# Sheet_2_nizovie.net
KiCad netlist of a schematic drawn in Altium Designer
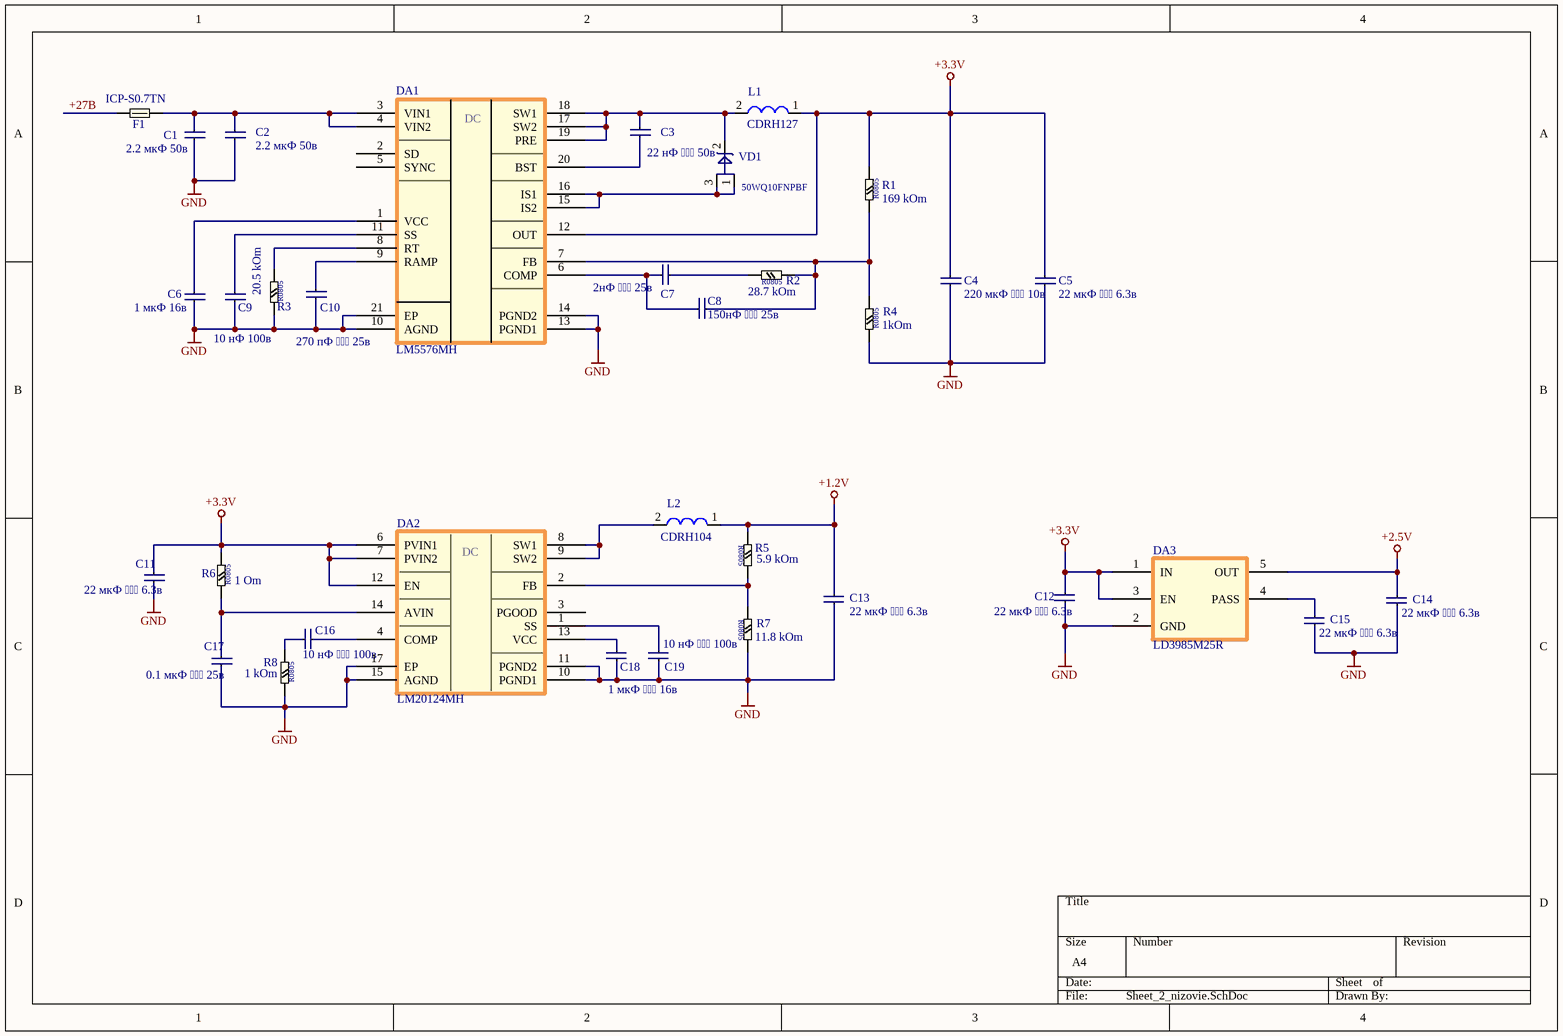
[diagram p0: Sheet_2_nizovie.SchDoc]

(export (version "E")
  (design (tool "Eeschema 10.0.6"))
  (components
    (comp (ref "C1")
      (value "2.2 мкФ 50в")
      (footprint "FP_0805")
      (libsource (lib "Schlib_nizovie") (part "C0805"))
    )
    (comp (ref "C2")
      (value "2.2 мкФ 50в")
      (footprint "FP_0805")
      (libsource (lib "Schlib_nizovie") (part "C0805"))
    )
    (comp (ref "C3")
      (value "22 нФ  50в")
      (footprint "FP_0805")
      (libsource (lib "Schlib_nizovie") (part "C0805"))
    )
    (comp (ref "C4")
      (value "220 мкФ  10в")
      (footprint "TYPE_D")
      (libsource (lib "Schlib_nizovie") (part "C0805"))
    )
    (comp (ref "C5")
      (value "22 мкФ  6.3в")
      (footprint "FP_0805")
      (libsource (lib "Schlib_nizovie") (part "C0805"))
    )
    (comp (ref "C6")
      (value "1 мкФ 16в")
      (footprint "FP_0805")
      (libsource (lib "Schlib_nizovie") (part "C0805"))
    )
    (comp (ref "C7")
      (value "2нФ  25в")
      (footprint "FP_0805")
      (libsource (lib "Schlib_nizovie") (part "C0805"))
    )
    (comp (ref "C8")
      (value "150нФ  25в")
      (footprint "FP_0805")
      (libsource (lib "Schlib_nizovie") (part "C0805"))
    )
    (comp (ref "C9")
      (value "10 нФ 100в")
      (footprint "FP_0805")
      (libsource (lib "Schlib_nizovie") (part "C0805"))
    )
    (comp (ref "C10")
      (value "270 пФ  25в")
      (footprint "FP_0805")
      (libsource (lib "Schlib_nizovie") (part "C0805"))
    )
    (comp (ref "C11")
      (value "22 мкФ  6.3в")
      (footprint "FP_0805")
      (libsource (lib "Schlib_nizovie") (part "C0805"))
    )
    (comp (ref "C12")
      (value "22 мкФ  6.3в")
      (footprint "FP_0805")
      (libsource (lib "Schlib_nizovie") (part "C0805"))
    )
    (comp (ref "C13")
      (value "22 мкФ  6.3в")
      (footprint "FP_0805")
      (libsource (lib "Schlib_nizovie") (part "C0805"))
    )
    (comp (ref "C14")
      (value "22 мкФ  6.3в")
      (footprint "FP_0805")
      (libsource (lib "Schlib_nizovie") (part "C0805"))
    )
    (comp (ref "C15")
      (value "22 мкФ  6.3в")
      (footprint "FP_0805")
      (libsource (lib "Schlib_nizovie") (part "C0805"))
    )
    (comp (ref "C16")
      (value "10 нФ  100в")
      (footprint "FP_0805")
      (libsource (lib "Schlib_nizovie") (part "C0805"))
    )
    (comp (ref "C17")
      (value "0.1 мкФ  25в")
      (footprint "FP_0805")
      (libsource (lib "Schlib_nizovie") (part "C0805"))
    )
    (comp (ref "C18")
      (value "1 мкФ  16в")
      (footprint "FP_0805")
      (libsource (lib "Schlib_nizovie") (part "C0805"))
    )
    (comp (ref "C19")
      (value "10 нФ  100в")
      (footprint "FP_0805")
      (libsource (lib "Schlib_nizovie") (part "C0805"))
    )
    (comp (ref "DA1")
      (value "LM5576MH")
      (footprint "LM5576")
      (libsource (lib "Schlib_nizovie") (part "LM5576MH"))
    )
    (comp (ref "DA2")
      (value "LM20124MH")
      (footprint "LM20124")
      (libsource (lib "Schlib_nizovie") (part "LM20124MH"))
    )
    (comp (ref "DA3")
      (value "LD3985M25R")
      (footprint "LD3985")
      (libsource (lib "Schlib_nizovie") (part "LD3985M25R"))
    )
    (comp (ref "F1")
      (value "ICP-S0.7TN")
      (footprint "ICP-S0.7")
      (libsource (lib "Schlib_nizovie") (part "ICP-S0.7TN"))
    )
    (comp (ref "L1")
      (value "CDRH127")
      (footprint "CDRH127")
      (libsource (lib "Schlib_nizovie") (part "CDRH127"))
    )
    (comp (ref "L2")
      (value "CDRH104")
      (footprint "CDRH104R")
      (libsource (lib "Schlib_nizovie") (part "CDRH104"))
    )
    (comp (ref "R1")
      (value "169 kOm")
      (footprint "FP_0805")
      (description "1kOm")
      (libsource (lib "Schlib_nizovie") (part "R0805"))
    )
    (comp (ref "R2")
      (value "28.7 kOm")
      (footprint "FP_0805")
      (description "1kOm")
      (libsource (lib "") (part "R0805_2"))
    )
    (comp (ref "R3")
      (value "20.5 kOm")
      (footprint "FP_0805")
      (description "1kOm")
      (libsource (lib "Schlib_nizovie") (part "R0805"))
    )
    (comp (ref "R4") (value "1kOm") (footprint "FP_0805") (libsource (lib "Schlib_nizovie") (part "R0805")))
    (comp (ref "R5")
      (value "5.9 kOm")
      (footprint "FP_0805")
      (description "1kOm")
      (libsource (lib "") (part "R0805_1"))
    )
    (comp (ref "R6")
      (value "1 Om")
      (footprint "FP_0805")
      (description "1kOm")
      (libsource (lib "Schlib_nizovie") (part "R0805"))
    )
    (comp (ref "R7")
      (value "11.8 kOm")
      (footprint "FP_0805")
      (description "1kOm")
      (libsource (lib "") (part "R0805_1"))
    )
    (comp (ref "R8")
      (value "1 kOm")
      (footprint "FP_0805")
      (description "1kOm")
      (libsource (lib "Schlib_nizovie") (part "R0805"))
    )
    (comp (ref "VD1")
      (value "50WQ10FNPBF")
      (footprint "50WQ06")
      (libsource (lib "Schlib_nizovie") (part "50WQ10FNPBF"))
    )
  )
  (nets
    (net (code "1") (name "+1.2V") (class "Default")
      (node (ref "C13") (pin "1") (pinfunction "1_1") (pintype "passive"))
      (node (ref "L2") (pin "1") (pinfunction "1_1") (pintype "passive"))
      (node (ref "R5") (pin "1") (pinfunction "1_1") (pintype "passive"))
    )
    (net (code "2") (name "+2.5V") (class "Default")
      (node (ref "C14") (pin "1") (pinfunction "1_1") (pintype "passive"))
      (node (ref "DA3") (pin "5") (pinfunction "OUT_5") (pintype "passive"))
    )
    (net (code "3") (name "+3.3V") (class "Default")
      (node (ref "C11") (pin "2") (pinfunction "2_2") (pintype "passive"))
      (node (ref "C12") (pin "1") (pinfunction "1_1") (pintype "passive"))
      (node (ref "C4") (pin "2") (pinfunction "2_2") (pintype "passive"))
      (node (ref "C5") (pin "2") (pinfunction "2_2") (pintype "passive"))
      (node (ref "DA1") (pin "12") (pinfunction "OUT_12") (pintype "passive"))
      (node (ref "DA2") (pin "12") (pinfunction "EN_12") (pintype "passive"))
      (node (ref "DA2") (pin "6") (pinfunction "PVIN1_6") (pintype "passive"))
      (node (ref "DA2") (pin "7") (pinfunction "PVIN2_7") (pintype "passive"))
      (node (ref "DA3") (pin "1") (pinfunction "IN_1") (pintype "passive"))
      (node (ref "DA3") (pin "3") (pinfunction "EN_3") (pintype "passive"))
      (node (ref "L1") (pin "1") (pinfunction "1_1") (pintype "passive"))
      (node (ref "R1") (pin "2") (pinfunction "2_2") (pintype "passive"))
      (node (ref "R6") (pin "2") (pinfunction "2_2") (pintype "passive"))
    )
    (net (code "4") (name "/+27В") (class "Default")
      (node (ref "F1") (pin "1") (pinfunction "1_1") (pintype "passive"))
    )
    (net (code "5") (name "GND") (class "Default")
      (node (ref "C1") (pin "1") (pinfunction "1_1") (pintype "passive"))
      (node (ref "C10") (pin "1") (pinfunction "1_1") (pintype "passive"))
      (node (ref "C11") (pin "1") (pinfunction "1_1") (pintype "passive"))
      (node (ref "C12") (pin "2") (pinfunction "2_2") (pintype "passive"))
      (node (ref "C13") (pin "2") (pinfunction "2_2") (pintype "passive"))
      (node (ref "C14") (pin "2") (pinfunction "2_2") (pintype "passive"))
      (node (ref "C15") (pin "2") (pinfunction "2_2") (pintype "passive"))
      (node (ref "C17") (pin "1") (pinfunction "1_1") (pintype "passive"))
      (node (ref "C18") (pin "2") (pinfunction "2_2") (pintype "passive"))
      (node (ref "C19") (pin "2") (pinfunction "2_2") (pintype "passive"))
      (node (ref "C2") (pin "1") (pinfunction "1_1") (pintype "passive"))
      (node (ref "C4") (pin "1") (pinfunction "1_1") (pintype "passive"))
      (node (ref "C5") (pin "1") (pinfunction "1_1") (pintype "passive"))
      (node (ref "C6") (pin "1") (pinfunction "1_1") (pintype "passive"))
      (node (ref "C9") (pin "1") (pinfunction "1_1") (pintype "passive"))
      (node (ref "DA1") (pin "10") (pinfunction "AGND_10") (pintype "passive"))
      (node (ref "DA1") (pin "13") (pinfunction "PGND1_13") (pintype "passive"))
      (node (ref "DA1") (pin "14") (pinfunction "PGND2_14") (pintype "passive"))
      (node (ref "DA1") (pin "21") (pinfunction "EP_21") (pintype "passive"))
      (node (ref "DA2") (pin "10") (pinfunction "PGND1_10") (pintype "passive"))
      (node (ref "DA2") (pin "11") (pinfunction "PGND2_11") (pintype "passive"))
      (node (ref "DA2") (pin "15") (pinfunction "AGND_15") (pintype "passive"))
      (node (ref "DA2") (pin "17") (pinfunction "EP_17") (pintype "passive"))
      (node (ref "DA3") (pin "2") (pinfunction "GND_2") (pintype "passive"))
      (node (ref "R3") (pin "1") (pinfunction "1_1") (pintype "passive"))
      (node (ref "R4") (pin "1") (pinfunction "1_1") (pintype "passive"))
      (node (ref "R7") (pin "2") (pinfunction "2_2") (pintype "passive"))
      (node (ref "R8") (pin "1") (pinfunction "1_1") (pintype "passive"))
    )
    (net (code "6") (name "Net-(C7-Pad1)") (class "Default")
      (node (ref "C7") (pin "1") (pinfunction "1_1") (pintype "passive"))
      (node (ref "R2") (pin "1") (pinfunction "1_1") (pintype "passive"))
    )
    (net (code "7") (name "Net-(C16-Pad2)") (class "Default")
      (node (ref "C16") (pin "2") (pinfunction "2_2") (pintype "passive"))
      (node (ref "R8") (pin "2") (pinfunction "2_2") (pintype "passive"))
    )
    (net (code "8") (name "Net-(DA1-BST)") (class "Default")
      (node (ref "C3") (pin "1") (pinfunction "1_1") (pintype "passive"))
      (node (ref "DA1") (pin "20") (pinfunction "BST_20") (pintype "passive"))
    )
    (net (code "9") (name "Net-(DA1-COMP)") (class "Default")
      (node (ref "C7") (pin "2") (pinfunction "2_2") (pintype "passive"))
      (node (ref "C8") (pin "2") (pinfunction "2_2") (pintype "passive"))
      (node (ref "DA1") (pin "6") (pinfunction "COMP_6") (pintype "passive"))
    )
    (net (code "10") (name "Net-(DA1-FB)") (class "Default")
      (node (ref "C8") (pin "1") (pinfunction "1_1") (pintype "passive"))
      (node (ref "DA1") (pin "7") (pinfunction "FB_7") (pintype "passive"))
      (node (ref "R1") (pin "1") (pinfunction "1_1") (pintype "passive"))
      (node (ref "R2") (pin "2") (pinfunction "2_2") (pintype "passive"))
      (node (ref "R4") (pin "2") (pinfunction "2_2") (pintype "passive"))
    )
    (net (code "11") (name "Net-(DA1-IS1)") (class "Default")
      (node (ref "DA1") (pin "15") (pinfunction "IS2_15") (pintype "passive"))
      (node (ref "DA1") (pin "16") (pinfunction "IS1_16") (pintype "passive"))
      (node (ref "VD1") (pin "1") (pinfunction "1_1") (pintype "passive"))
      (node (ref "VD1") (pin "3") (pinfunction "3_3") (pintype "passive"))
    )
    (net (code "12") (name "Net-(DA1-PRE)") (class "Default")
      (node (ref "C3") (pin "2") (pinfunction "2_2") (pintype "passive"))
      (node (ref "DA1") (pin "17") (pinfunction "SW2_17") (pintype "passive"))
      (node (ref "DA1") (pin "18") (pinfunction "SW1_18") (pintype "passive"))
      (node (ref "DA1") (pin "19") (pinfunction "PRE_19") (pintype "passive"))
      (node (ref "L1") (pin "2") (pinfunction "2_2") (pintype "passive"))
      (node (ref "VD1") (pin "2") (pinfunction "2_2") (pintype "passive"))
    )
    (net (code "13") (name "Net-(DA1-RAMP)") (class "Default")
      (node (ref "C10") (pin "2") (pinfunction "2_2") (pintype "passive"))
      (node (ref "DA1") (pin "9") (pinfunction "RAMP_9") (pintype "passive"))
    )
    (net (code "14") (name "Net-(DA1-RT)") (class "Default")
      (node (ref "DA1") (pin "8") (pinfunction "RT_8") (pintype "passive"))
      (node (ref "R3") (pin "2") (pinfunction "2_2") (pintype "passive"))
    )
    (net (code "15") (name "Net-(DA1-SS)") (class "Default")
      (node (ref "C9") (pin "2") (pinfunction "2_2") (pintype "passive"))
      (node (ref "DA1") (pin "11") (pinfunction "SS_11") (pintype "passive"))
    )
    (net (code "16") (name "Net-(DA1-VCC)") (class "Default")
      (node (ref "C6") (pin "2") (pinfunction "2_2") (pintype "passive"))
      (node (ref "DA1") (pin "1") (pinfunction "VCC_1") (pintype "passive"))
    )
    (net (code "17") (name "Net-(DA1-VIN1)") (class "Default")
      (node (ref "C1") (pin "2") (pinfunction "2_2") (pintype "passive"))
      (node (ref "C2") (pin "2") (pinfunction "2_2") (pintype "passive"))
      (node (ref "DA1") (pin "3") (pinfunction "VIN1_3") (pintype "passive"))
      (node (ref "DA1") (pin "4") (pinfunction "VIN2_4") (pintype "passive"))
      (node (ref "F1") (pin "2") (pinfunction "2_2") (pintype "passive"))
    )
    (net (code "18") (name "Net-(DA2-AVIN)") (class "Default")
      (node (ref "C17") (pin "2") (pinfunction "2_2") (pintype "passive"))
      (node (ref "DA2") (pin "14") (pinfunction "AVIN_14") (pintype "passive"))
      (node (ref "R6") (pin "1") (pinfunction "1_1") (pintype "passive"))
    )
    (net (code "19") (name "Net-(DA2-COMP)") (class "Default")
      (node (ref "C16") (pin "1") (pinfunction "1_1") (pintype "passive"))
      (node (ref "DA2") (pin "4") (pinfunction "COMP_4") (pintype "passive"))
    )
    (net (code "20") (name "Net-(DA2-FB)") (class "Default")
      (node (ref "DA2") (pin "2") (pinfunction "FB_2") (pintype "passive"))
      (node (ref "R5") (pin "2") (pinfunction "2_2") (pintype "passive"))
      (node (ref "R7") (pin "1") (pinfunction "1_1") (pintype "passive"))
    )
    (net (code "21") (name "Net-(DA2-SS)") (class "Default")
      (node (ref "C19") (pin "1") (pinfunction "1_1") (pintype "passive"))
      (node (ref "DA2") (pin "1") (pinfunction "SS_1") (pintype "passive"))
    )
    (net (code "22") (name "Net-(DA2-SW1)") (class "Default")
      (node (ref "DA2") (pin "8") (pinfunction "SW1_8") (pintype "passive"))
      (node (ref "DA2") (pin "9") (pinfunction "SW2_9") (pintype "passive"))
      (node (ref "L2") (pin "2") (pinfunction "2_2") (pintype "passive"))
    )
    (net (code "23") (name "Net-(DA2-VCC)") (class "Default")
      (node (ref "C18") (pin "1") (pinfunction "1_1") (pintype "passive"))
      (node (ref "DA2") (pin "13") (pinfunction "VCC_13") (pintype "passive"))
    )
    (net (code "24") (name "Net-(DA3-PASS)") (class "Default")
      (node (ref "C15") (pin "1") (pinfunction "1_1") (pintype "passive"))
      (node (ref "DA3") (pin "4") (pinfunction "PASS_4") (pintype "passive"))
    )
    (net (code "25") (name "unconnected-(DA1-SD-Pad2)") (class "Default")
      (node (ref "DA1") (pin "2") (pinfunction "SD_2") (pintype "passive"))
    )
    (net (code "26") (name "unconnected-(DA1-SYNC-Pad5)") (class "Default")
      (node (ref "DA1") (pin "5") (pinfunction "SYNC_5") (pintype "passive"))
    )
    (net (code "27") (name "unconnected-(DA2-PGOOD-Pad3)") (class "Default")
      (node (ref "DA2") (pin "3") (pinfunction "PGOOD_3") (pintype "passive"))
    )
  )
)
